# dashboard.net
KiCad netlist of a schematic drawn in EAGLE
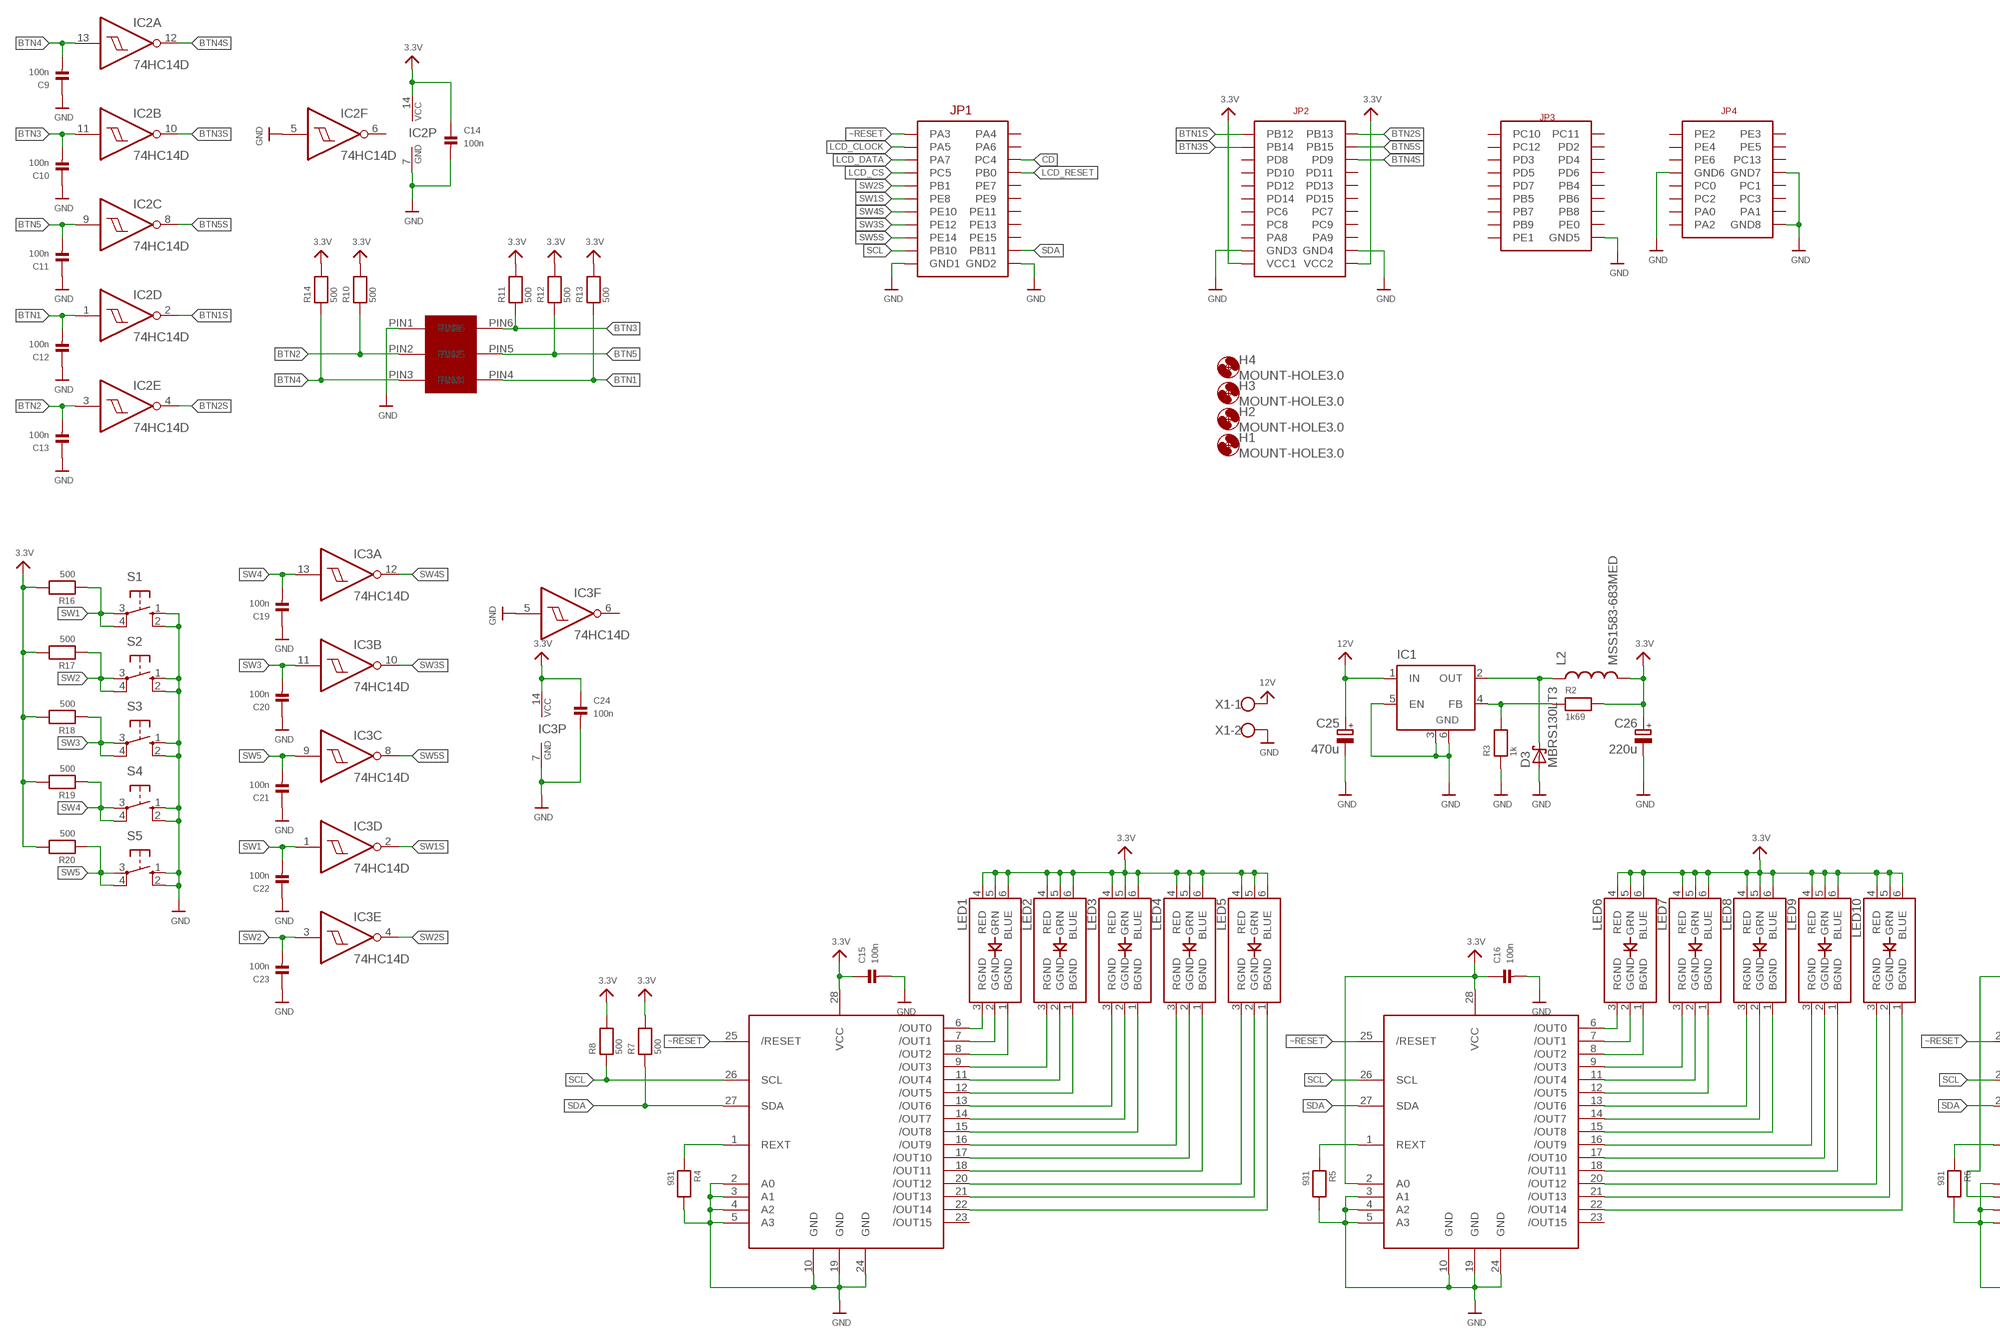
[diagram p0: schematic, sheet 1, part 1 of 2]
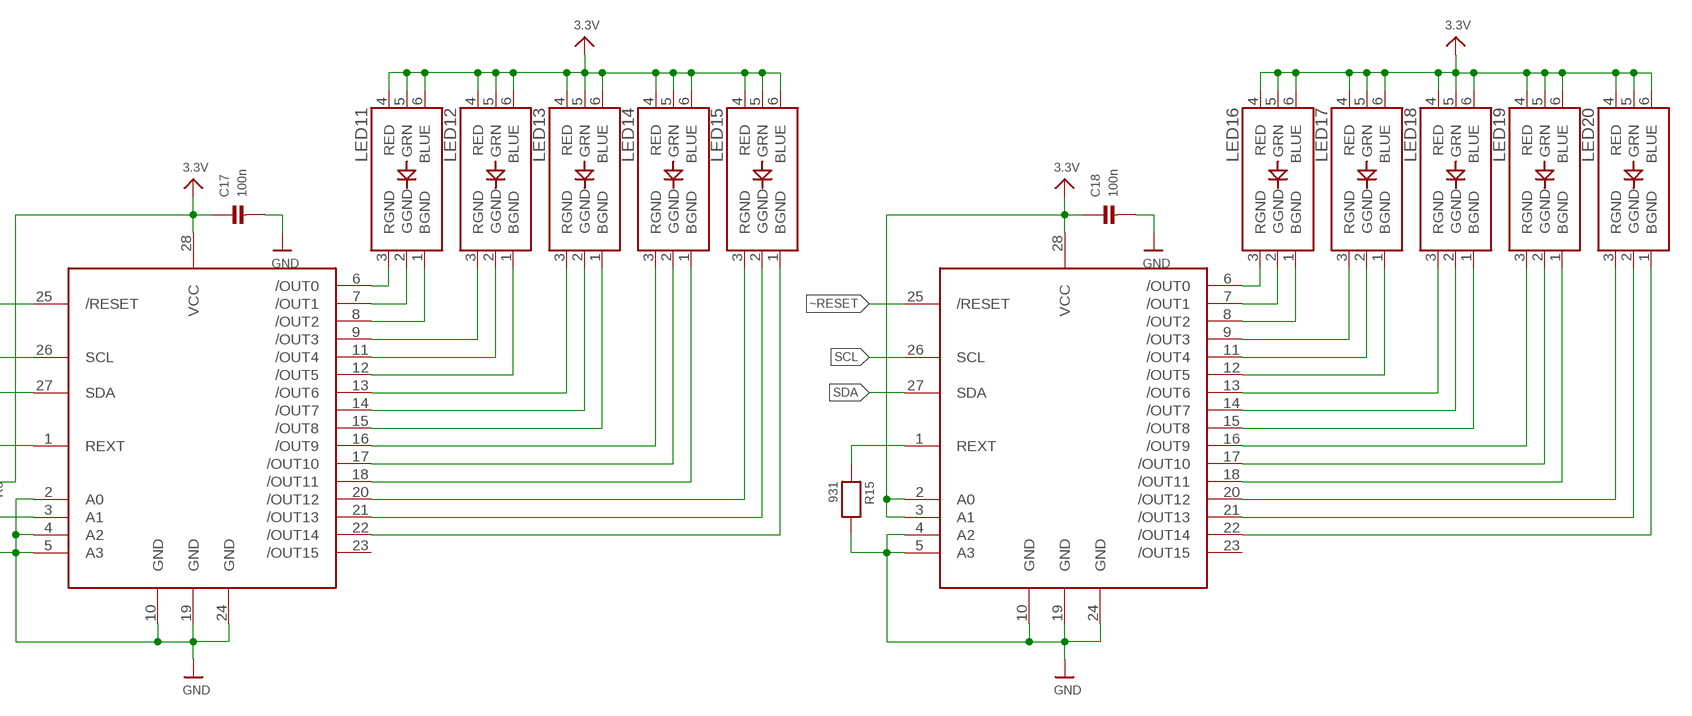
[diagram p1: schematic, sheet 1, part 2 of 2]

(export (version "E")
  (design (tool "Eeschema 10.0.6"))
  (components
    (comp (ref "C9")
      (value "100n")
      (footprint "eagle-import:_0603")
      (libsource (lib "eagle-import") (part "CAP_CERAMIC_0603"))
    )
    (comp (ref "C10")
      (value "100n")
      (footprint "eagle-import:_0603")
      (libsource (lib "eagle-import") (part "CAP_CERAMIC_0603"))
    )
    (comp (ref "C11")
      (value "100n")
      (footprint "eagle-import:_0603")
      (libsource (lib "eagle-import") (part "CAP_CERAMIC_0603"))
    )
    (comp (ref "C12")
      (value "100n")
      (footprint "eagle-import:_0603")
      (libsource (lib "eagle-import") (part "CAP_CERAMIC_0603"))
    )
    (comp (ref "C13")
      (value "100n")
      (footprint "eagle-import:_0603")
      (libsource (lib "eagle-import") (part "CAP_CERAMIC_0603"))
    )
    (comp (ref "C14")
      (value "100n")
      (footprint "eagle-import:_0603")
      (libsource (lib "eagle-import") (part "CAP_CERAMIC_0603"))
    )
    (comp (ref "C15")
      (value "100n")
      (footprint "eagle-import:_0603")
      (libsource (lib "eagle-import") (part "CAP_CERAMIC_0603"))
    )
    (comp (ref "C16")
      (value "100n")
      (footprint "eagle-import:_0603")
      (libsource (lib "eagle-import") (part "CAP_CERAMIC_0603"))
    )
    (comp (ref "C17")
      (value "100n")
      (footprint "eagle-import:_0603")
      (libsource (lib "eagle-import") (part "CAP_CERAMIC_0603"))
    )
    (comp (ref "C18")
      (value "100n")
      (footprint "eagle-import:_0603")
      (libsource (lib "eagle-import") (part "CAP_CERAMIC_0603"))
    )
    (comp (ref "C19")
      (value "100n")
      (footprint "eagle-import:_0603")
      (libsource (lib "eagle-import") (part "CAP_CERAMIC_0603"))
    )
    (comp (ref "C20")
      (value "100n")
      (footprint "eagle-import:_0603")
      (libsource (lib "eagle-import") (part "CAP_CERAMIC_0603"))
    )
    (comp (ref "C21")
      (value "100n")
      (footprint "eagle-import:_0603")
      (libsource (lib "eagle-import") (part "CAP_CERAMIC_0603"))
    )
    (comp (ref "C22")
      (value "100n")
      (footprint "eagle-import:_0603")
      (libsource (lib "eagle-import") (part "CAP_CERAMIC_0603"))
    )
    (comp (ref "C23")
      (value "100n")
      (footprint "eagle-import:_0603")
      (libsource (lib "eagle-import") (part "CAP_CERAMIC_0603"))
    )
    (comp (ref "C24")
      (value "100n")
      (footprint "eagle-import:_0603")
      (libsource (lib "eagle-import") (part "CAP_CERAMIC_0603"))
    )
    (comp (ref "C25")
      (value "470u")
      (footprint "eagle-import:153CLV-1012")
      (libsource (lib "eagle-import") (part "CPOL-EU153CLV-1012"))
    )
    (comp (ref "C26")
      (value "220u")
      (footprint "eagle-import:153CLV-1012")
      (libsource (lib "eagle-import") (part "CPOL-EU153CLV-1012"))
    )
    (comp (ref "D3")
      (value "MBRS130LT3")
      (footprint "eagle-import:SMB")
      (libsource (lib "eagle-import") (part "MBRS130LT3"))
    )
    (comp (ref "H1")
      (value "MOUNT-HOLE3.0")
      (footprint "eagle-import:3,0")
      (libsource (lib "eagle-import") (part "MOUNT-HOLE3.0"))
    )
    (comp (ref "H2")
      (value "MOUNT-HOLE3.0")
      (footprint "eagle-import:3,0")
      (libsource (lib "eagle-import") (part "MOUNT-HOLE3.0"))
    )
    (comp (ref "H3")
      (value "MOUNT-HOLE3.0")
      (footprint "eagle-import:3,0")
      (libsource (lib "eagle-import") (part "MOUNT-HOLE3.0"))
    )
    (comp (ref "H4")
      (value "MOUNT-HOLE3.0")
      (footprint "eagle-import:3,0")
      (libsource (lib "eagle-import") (part "MOUNT-HOLE3.0"))
    )
    (comp (ref "IC1")
      (value "LM2596S")
      (footprint "eagle-import:TO263-5")
      (libsource (lib "eagle-import") (part "LM2596S"))
    )
    (comp (ref "IC2")
      (value "74HC14D")
      (footprint "eagle-import:SO14")
      (libsource (lib "eagle-import") (part "7414DHC"))
    )
    (comp (ref "IC3")
      (value "74HC14D")
      (footprint "eagle-import:SO14")
      (libsource (lib "eagle-import") (part "7414DHC"))
    )
    (comp (ref "L2")
      (value "MSS1583-683MED")
      (footprint "eagle-import:CDRH125")
      (libsource (lib "eagle-import") (part "INDUCTORPWR"))
    )
    (comp (ref "LED1")
      (value "LED_RGB_PLCC6CREE-CLV6A")
      (footprint "eagle-import:RGBLED_PLCC6")
      (libsource (lib "eagle-import") (part "LED_RGB_PLCC6CREE-CLV6A"))
    )
    (comp (ref "LED2")
      (value "LED_RGB_PLCC6CREE-CLV6A")
      (footprint "eagle-import:RGBLED_PLCC6")
      (libsource (lib "eagle-import") (part "LED_RGB_PLCC6CREE-CLV6A"))
    )
    (comp (ref "LED3")
      (value "LED_RGB_PLCC6CREE-CLV6A")
      (footprint "eagle-import:RGBLED_PLCC6")
      (libsource (lib "eagle-import") (part "LED_RGB_PLCC6CREE-CLV6A"))
    )
    (comp (ref "LED4")
      (value "LED_RGB_PLCC6CREE-CLV6A")
      (footprint "eagle-import:RGBLED_PLCC6")
      (libsource (lib "eagle-import") (part "LED_RGB_PLCC6CREE-CLV6A"))
    )
    (comp (ref "LED5")
      (value "LED_RGB_PLCC6CREE-CLV6A")
      (footprint "eagle-import:RGBLED_PLCC6")
      (libsource (lib "eagle-import") (part "LED_RGB_PLCC6CREE-CLV6A"))
    )
    (comp (ref "LED6")
      (value "LED_RGB_PLCC6CREE-CLV6A")
      (footprint "eagle-import:RGBLED_PLCC6")
      (libsource (lib "eagle-import") (part "LED_RGB_PLCC6CREE-CLV6A"))
    )
    (comp (ref "LED7")
      (value "LED_RGB_PLCC6CREE-CLV6A")
      (footprint "eagle-import:RGBLED_PLCC6")
      (libsource (lib "eagle-import") (part "LED_RGB_PLCC6CREE-CLV6A"))
    )
    (comp (ref "LED8")
      (value "LED_RGB_PLCC6CREE-CLV6A")
      (footprint "eagle-import:RGBLED_PLCC6")
      (libsource (lib "eagle-import") (part "LED_RGB_PLCC6CREE-CLV6A"))
    )
    (comp (ref "LED9")
      (value "LED_RGB_PLCC6CREE-CLV6A")
      (footprint "eagle-import:RGBLED_PLCC6")
      (libsource (lib "eagle-import") (part "LED_RGB_PLCC6CREE-CLV6A"))
    )
    (comp (ref "LED10")
      (value "LED_RGB_PLCC6CREE-CLV6A")
      (footprint "eagle-import:RGBLED_PLCC6")
      (libsource (lib "eagle-import") (part "LED_RGB_PLCC6CREE-CLV6A"))
    )
    (comp (ref "LED11")
      (value "LED_RGB_PLCC6CREE-CLV6A")
      (footprint "eagle-import:RGBLED_PLCC6")
      (libsource (lib "eagle-import") (part "LED_RGB_PLCC6CREE-CLV6A"))
    )
    (comp (ref "LED12")
      (value "LED_RGB_PLCC6CREE-CLV6A")
      (footprint "eagle-import:RGBLED_PLCC6")
      (libsource (lib "eagle-import") (part "LED_RGB_PLCC6CREE-CLV6A"))
    )
    (comp (ref "LED13")
      (value "LED_RGB_PLCC6CREE-CLV6A")
      (footprint "eagle-import:RGBLED_PLCC6")
      (libsource (lib "eagle-import") (part "LED_RGB_PLCC6CREE-CLV6A"))
    )
    (comp (ref "LED14")
      (value "LED_RGB_PLCC6CREE-CLV6A")
      (footprint "eagle-import:RGBLED_PLCC6")
      (libsource (lib "eagle-import") (part "LED_RGB_PLCC6CREE-CLV6A"))
    )
    (comp (ref "LED15")
      (value "LED_RGB_PLCC6CREE-CLV6A")
      (footprint "eagle-import:RGBLED_PLCC6")
      (libsource (lib "eagle-import") (part "LED_RGB_PLCC6CREE-CLV6A"))
    )
    (comp (ref "LED16")
      (value "LED_RGB_PLCC6CREE-CLV6A")
      (footprint "eagle-import:RGBLED_PLCC6")
      (libsource (lib "eagle-import") (part "LED_RGB_PLCC6CREE-CLV6A"))
    )
    (comp (ref "LED17")
      (value "LED_RGB_PLCC6CREE-CLV6A")
      (footprint "eagle-import:RGBLED_PLCC6")
      (libsource (lib "eagle-import") (part "LED_RGB_PLCC6CREE-CLV6A"))
    )
    (comp (ref "LED18")
      (value "LED_RGB_PLCC6CREE-CLV6A")
      (footprint "eagle-import:RGBLED_PLCC6")
      (libsource (lib "eagle-import") (part "LED_RGB_PLCC6CREE-CLV6A"))
    )
    (comp (ref "LED19")
      (value "LED_RGB_PLCC6CREE-CLV6A")
      (footprint "eagle-import:RGBLED_PLCC6")
      (libsource (lib "eagle-import") (part "LED_RGB_PLCC6CREE-CLV6A"))
    )
    (comp (ref "LED20")
      (value "LED_RGB_PLCC6CREE-CLV6A")
      (footprint "eagle-import:RGBLED_PLCC6")
      (libsource (lib "eagle-import") (part "LED_RGB_PLCC6CREE-CLV6A"))
    )
    (comp (ref "R2")
      (value "1k69")
      (footprint "eagle-import:_0603")
      (libsource (lib "eagle-import") (part "RESISTOR_0603"))
    )
    (comp (ref "R3")
      (value "1k")
      (footprint "eagle-import:_0603")
      (libsource (lib "eagle-import") (part "RESISTOR_0603"))
    )
    (comp (ref "R4")
      (value "931")
      (footprint "eagle-import:_0603")
      (libsource (lib "eagle-import") (part "RESISTOR_0603"))
    )
    (comp (ref "R5")
      (value "931")
      (footprint "eagle-import:_0603")
      (libsource (lib "eagle-import") (part "RESISTOR_0603"))
    )
    (comp (ref "R6")
      (value "931")
      (footprint "eagle-import:_0603")
      (libsource (lib "eagle-import") (part "RESISTOR_0603"))
    )
    (comp (ref "R7")
      (value "500")
      (footprint "eagle-import:_0603")
      (libsource (lib "eagle-import") (part "RESISTOR_0603"))
    )
    (comp (ref "R8")
      (value "500")
      (footprint "eagle-import:_0603")
      (libsource (lib "eagle-import") (part "RESISTOR_0603"))
    )
    (comp (ref "R10")
      (value "500")
      (footprint "eagle-import:_0603")
      (libsource (lib "eagle-import") (part "RESISTOR_0603"))
    )
    (comp (ref "R11")
      (value "500")
      (footprint "eagle-import:_0603")
      (libsource (lib "eagle-import") (part "RESISTOR_0603"))
    )
    (comp (ref "R12")
      (value "500")
      (footprint "eagle-import:_0603")
      (libsource (lib "eagle-import") (part "RESISTOR_0603"))
    )
    (comp (ref "R13")
      (value "500")
      (footprint "eagle-import:_0603")
      (libsource (lib "eagle-import") (part "RESISTOR_0603"))
    )
    (comp (ref "R14")
      (value "500")
      (footprint "eagle-import:_0603")
      (libsource (lib "eagle-import") (part "RESISTOR_0603"))
    )
    (comp (ref "R15")
      (value "931")
      (footprint "eagle-import:_0603")
      (libsource (lib "eagle-import") (part "RESISTOR_0603"))
    )
    (comp (ref "R16")
      (value "500")
      (footprint "eagle-import:_0603")
      (libsource (lib "eagle-import") (part "RESISTOR_0603"))
    )
    (comp (ref "R17")
      (value "500")
      (footprint "eagle-import:_0603")
      (libsource (lib "eagle-import") (part "RESISTOR_0603"))
    )
    (comp (ref "R18")
      (value "500")
      (footprint "eagle-import:_0603")
      (libsource (lib "eagle-import") (part "RESISTOR_0603"))
    )
    (comp (ref "R19")
      (value "500")
      (footprint "eagle-import:_0603")
      (libsource (lib "eagle-import") (part "RESISTOR_0603"))
    )
    (comp (ref "R20")
      (value "500")
      (footprint "eagle-import:_0603")
      (libsource (lib "eagle-import") (part "RESISTOR_0603"))
    )
    (comp (ref "S1")
      (value "10-XX")
      (footprint "eagle-import:B3F-10XX")
      (fields (field (name "MPN") "B3F-1000"))
      (libsource (lib "eagle-import") (part "10-XX"))
    )
    (comp (ref "S2")
      (value "10-XX")
      (footprint "eagle-import:B3F-10XX")
      (fields (field (name "MPN") "B3F-1000"))
      (libsource (lib "eagle-import") (part "10-XX"))
    )
    (comp (ref "S3")
      (value "10-XX")
      (footprint "eagle-import:B3F-10XX")
      (fields (field (name "MPN") "B3F-1000"))
      (libsource (lib "eagle-import") (part "10-XX"))
    )
    (comp (ref "S4")
      (value "10-XX")
      (footprint "eagle-import:B3F-10XX")
      (fields (field (name "MPN") "B3F-1000"))
      (libsource (lib "eagle-import") (part "10-XX"))
    )
    (comp (ref "S5")
      (value "10-XX")
      (footprint "eagle-import:B3F-10XX")
      (fields
        (field (name "MPN") "B3F-1000")
        (field (name "MPN_1") "B3F-1000")
        (field (name "OC_FARNELL") "176432")
        (field (name "OC_NEWARK") "36M3542")
      )
      (libsource (lib "eagle-import") (part "10-XX"))
    )
    (comp (ref "U$1")
      (value "CPU-BOARD")
      (footprint "eagle-import:CPU-BOARD-JP1")
      (libsource (lib "eagle-import") (part "CPU-BOARD"))
    )
    (comp (ref "U$30")
      (value "TLC59116")
      (footprint "eagle-import:TSSOP28")
      (libsource (lib "eagle-import") (part "TLC59116"))
    )
    (comp (ref "U$33")
      (value "TLC59116")
      (footprint "eagle-import:TSSOP28")
      (libsource (lib "eagle-import") (part "TLC59116"))
    )
    (comp (ref "U$36")
      (value "TLC59116")
      (footprint "eagle-import:TSSOP28")
      (libsource (lib "eagle-import") (part "TLC59116"))
    )
    (comp (ref "U$42")
      (value "MICROFIT6")
      (footprint "eagle-import:MICROFIT6SOCK")
      (libsource (lib "eagle-import") (part "MICROFIT6"))
    )
    (comp (ref "U$51")
      (value "TLC59116")
      (footprint "eagle-import:TSSOP28")
      (libsource (lib "eagle-import") (part "TLC59116"))
    )
    (comp (ref "X1")
      (value "W237-102")
      (footprint "eagle-import:W237-102")
      (fields (field (name "MPN") "237-102"))
      (libsource (lib "eagle-import") (part "W237-102"))
    )
  )
  (nets
    (net (code "1") (name "/~{RESET}") (class "Default")
      (node (ref "U$1") (pin "P$1") (pinfunction "PA3_P$1") (pintype "bidirectional"))
      (node (ref "U$30") (pin "25") (pinfunction "/RESET_25") (pintype "bidirectional"))
      (node (ref "U$33") (pin "25") (pinfunction "/RESET_25") (pintype "bidirectional"))
      (node (ref "U$36") (pin "25") (pinfunction "/RESET_25") (pintype "bidirectional"))
      (node (ref "U$51") (pin "25") (pinfunction "/RESET_25") (pintype "bidirectional"))
    )
    (net (code "2") (name "3.3V") (class "Default")
      (node (ref "C14") (pin "1") (pinfunction "P$1_1") (pintype "passive"))
      (node (ref "C15") (pin "1") (pinfunction "P$1_1") (pintype "passive"))
      (node (ref "C16") (pin "1") (pinfunction "P$1_1") (pintype "passive"))
      (node (ref "C17") (pin "1") (pinfunction "P$1_1") (pintype "passive"))
      (node (ref "C18") (pin "1") (pinfunction "P$1_1") (pintype "passive"))
      (node (ref "C24") (pin "1") (pinfunction "P$1_1") (pintype "passive"))
      (node (ref "C26") (pin "+") (pinfunction "+_+") (pintype "passive"))
      (node (ref "IC2") (pin "14") (pinfunction "VCC_14") (pintype "power_in"))
      (node (ref "IC3") (pin "14") (pinfunction "VCC_14") (pintype "power_in"))
      (node (ref "L2") (pin "2") (pinfunction "2_2") (pintype "passive"))
      (node (ref "LED1") (pin "4") (pinfunction "RED_4") (pintype "bidirectional"))
      (node (ref "LED1") (pin "5") (pinfunction "GRN_5") (pintype "bidirectional"))
      (node (ref "LED1") (pin "6") (pinfunction "BLUE_6") (pintype "bidirectional"))
      (node (ref "LED10") (pin "4") (pinfunction "RED_4") (pintype "bidirectional"))
      (node (ref "LED10") (pin "5") (pinfunction "GRN_5") (pintype "bidirectional"))
      (node (ref "LED10") (pin "6") (pinfunction "BLUE_6") (pintype "bidirectional"))
      (node (ref "LED11") (pin "4") (pinfunction "RED_4") (pintype "bidirectional"))
      (node (ref "LED11") (pin "5") (pinfunction "GRN_5") (pintype "bidirectional"))
      (node (ref "LED11") (pin "6") (pinfunction "BLUE_6") (pintype "bidirectional"))
      (node (ref "LED12") (pin "4") (pinfunction "RED_4") (pintype "bidirectional"))
      (node (ref "LED12") (pin "5") (pinfunction "GRN_5") (pintype "bidirectional"))
      (node (ref "LED12") (pin "6") (pinfunction "BLUE_6") (pintype "bidirectional"))
      (node (ref "LED13") (pin "4") (pinfunction "RED_4") (pintype "bidirectional"))
      (node (ref "LED13") (pin "5") (pinfunction "GRN_5") (pintype "bidirectional"))
      (node (ref "LED13") (pin "6") (pinfunction "BLUE_6") (pintype "bidirectional"))
      (node (ref "LED14") (pin "4") (pinfunction "RED_4") (pintype "bidirectional"))
      (node (ref "LED14") (pin "5") (pinfunction "GRN_5") (pintype "bidirectional"))
      (node (ref "LED14") (pin "6") (pinfunction "BLUE_6") (pintype "bidirectional"))
      (node (ref "LED15") (pin "4") (pinfunction "RED_4") (pintype "bidirectional"))
      (node (ref "LED15") (pin "5") (pinfunction "GRN_5") (pintype "bidirectional"))
      (node (ref "LED15") (pin "6") (pinfunction "BLUE_6") (pintype "bidirectional"))
      (node (ref "LED16") (pin "4") (pinfunction "RED_4") (pintype "bidirectional"))
      (node (ref "LED16") (pin "5") (pinfunction "GRN_5") (pintype "bidirectional"))
      (node (ref "LED16") (pin "6") (pinfunction "BLUE_6") (pintype "bidirectional"))
      (node (ref "LED17") (pin "4") (pinfunction "RED_4") (pintype "bidirectional"))
      (node (ref "LED17") (pin "5") (pinfunction "GRN_5") (pintype "bidirectional"))
      (node (ref "LED17") (pin "6") (pinfunction "BLUE_6") (pintype "bidirectional"))
      (node (ref "LED18") (pin "4") (pinfunction "RED_4") (pintype "bidirectional"))
      (node (ref "LED18") (pin "5") (pinfunction "GRN_5") (pintype "bidirectional"))
      (node (ref "LED18") (pin "6") (pinfunction "BLUE_6") (pintype "bidirectional"))
      (node (ref "LED19") (pin "4") (pinfunction "RED_4") (pintype "bidirectional"))
      (node (ref "LED19") (pin "5") (pinfunction "GRN_5") (pintype "bidirectional"))
      (node (ref "LED19") (pin "6") (pinfunction "BLUE_6") (pintype "bidirectional"))
      (node (ref "LED2") (pin "4") (pinfunction "RED_4") (pintype "bidirectional"))
      (node (ref "LED2") (pin "5") (pinfunction "GRN_5") (pintype "bidirectional"))
      (node (ref "LED2") (pin "6") (pinfunction "BLUE_6") (pintype "bidirectional"))
      (node (ref "LED20") (pin "4") (pinfunction "RED_4") (pintype "bidirectional"))
      (node (ref "LED20") (pin "5") (pinfunction "GRN_5") (pintype "bidirectional"))
      (node (ref "LED20") (pin "6") (pinfunction "BLUE_6") (pintype "bidirectional"))
      (node (ref "LED3") (pin "4") (pinfunction "RED_4") (pintype "bidirectional"))
      (node (ref "LED3") (pin "5") (pinfunction "GRN_5") (pintype "bidirectional"))
      (node (ref "LED3") (pin "6") (pinfunction "BLUE_6") (pintype "bidirectional"))
      (node (ref "LED4") (pin "4") (pinfunction "RED_4") (pintype "bidirectional"))
      (node (ref "LED4") (pin "5") (pinfunction "GRN_5") (pintype "bidirectional"))
      (node (ref "LED4") (pin "6") (pinfunction "BLUE_6") (pintype "bidirectional"))
      (node (ref "LED5") (pin "4") (pinfunction "RED_4") (pintype "bidirectional"))
      (node (ref "LED5") (pin "5") (pinfunction "GRN_5") (pintype "bidirectional"))
      (node (ref "LED5") (pin "6") (pinfunction "BLUE_6") (pintype "bidirectional"))
      (node (ref "LED6") (pin "4") (pinfunction "RED_4") (pintype "bidirectional"))
      (node (ref "LED6") (pin "5") (pinfunction "GRN_5") (pintype "bidirectional"))
      (node (ref "LED6") (pin "6") (pinfunction "BLUE_6") (pintype "bidirectional"))
      (node (ref "LED7") (pin "4") (pinfunction "RED_4") (pintype "bidirectional"))
      (node (ref "LED7") (pin "5") (pinfunction "GRN_5") (pintype "bidirectional"))
      (node (ref "LED7") (pin "6") (pinfunction "BLUE_6") (pintype "bidirectional"))
      (node (ref "LED8") (pin "4") (pinfunction "RED_4") (pintype "bidirectional"))
      (node (ref "LED8") (pin "5") (pinfunction "GRN_5") (pintype "bidirectional"))
      (node (ref "LED8") (pin "6") (pinfunction "BLUE_6") (pintype "bidirectional"))
      (node (ref "LED9") (pin "4") (pinfunction "RED_4") (pintype "bidirectional"))
      (node (ref "LED9") (pin "5") (pinfunction "GRN_5") (pintype "bidirectional"))
      (node (ref "LED9") (pin "6") (pinfunction "BLUE_6") (pintype "bidirectional"))
      (node (ref "R10") (pin "2") (pinfunction "2_2") (pintype "passive"))
      (node (ref "R11") (pin "2") (pinfunction "2_2") (pintype "passive"))
      (node (ref "R12") (pin "2") (pinfunction "2_2") (pintype "passive"))
      (node (ref "R13") (pin "2") (pinfunction "2_2") (pintype "passive"))
      (node (ref "R14") (pin "2") (pinfunction "2_2") (pintype "passive"))
      (node (ref "R16") (pin "2") (pinfunction "2_2") (pintype "passive"))
      (node (ref "R17") (pin "2") (pinfunction "2_2") (pintype "passive"))
      (node (ref "R18") (pin "2") (pinfunction "2_2") (pintype "passive"))
      (node (ref "R19") (pin "2") (pinfunction "2_2") (pintype "passive"))
      (node (ref "R2") (pin "2") (pinfunction "2_2") (pintype "passive"))
      (node (ref "R20") (pin "2") (pinfunction "2_2") (pintype "passive"))
      (node (ref "R7") (pin "2") (pinfunction "2_2") (pintype "passive"))
      (node (ref "R8") (pin "2") (pinfunction "2_2") (pintype "passive"))
      (node (ref "U$1") (pin "P$43") (pinfunction "VCC1_P$43") (pintype "bidirectional"))
      (node (ref "U$1") (pin "P$44") (pinfunction "VCC2_P$44") (pintype "bidirectional"))
      (node (ref "U$30") (pin "28") (pinfunction "VCC_28") (pintype "bidirectional"))
      (node (ref "U$33") (pin "2") (pinfunction "A0_2") (pintype "bidirectional"))
      (node (ref "U$33") (pin "28") (pinfunction "VCC_28") (pintype "bidirectional"))
      (node (ref "U$36") (pin "28") (pinfunction "VCC_28") (pintype "bidirectional"))
      (node (ref "U$36") (pin "3") (pinfunction "A1_3") (pintype "bidirectional"))
      (node (ref "U$51") (pin "2") (pinfunction "A0_2") (pintype "bidirectional"))
      (node (ref "U$51") (pin "28") (pinfunction "VCC_28") (pintype "bidirectional"))
      (node (ref "U$51") (pin "3") (pinfunction "A1_3") (pintype "bidirectional"))
    )
    (net (code "3") (name "12V") (class "Default")
      (node (ref "C25") (pin "+") (pinfunction "+_+") (pintype "passive"))
      (node (ref "IC1") (pin "1") (pinfunction "IN_1") (pintype "input"))
      (node (ref "X1") (pin "1") (pinfunction "KL_1") (pintype "passive"))
    )
    (net (code "4") (name "BTN1") (class "Default")
      (node (ref "C12") (pin "2") (pinfunction "P$2_2") (pintype "passive"))
      (node (ref "IC2") (pin "1") (pinfunction "I_1") (pintype "input"))
      (node (ref "R13") (pin "1") (pinfunction "1_1") (pintype "passive"))
      (node (ref "U$42") (pin "PIN4") (pinfunction "PIN4_PIN4") (pintype "bidirectional"))
    )
    (net (code "5") (name "BTN1S") (class "Default")
      (node (ref "IC2") (pin "2") (pinfunction "O_2") (pintype "output"))
      (node (ref "U$1") (pin "P$23") (pinfunction "PB12_P$23") (pintype "bidirectional"))
    )
    (net (code "6") (name "BTN2") (class "Default")
      (node (ref "C13") (pin "2") (pinfunction "P$2_2") (pintype "passive"))
      (node (ref "IC2") (pin "3") (pinfunction "I_3") (pintype "input"))
      (node (ref "R10") (pin "1") (pinfunction "1_1") (pintype "passive"))
      (node (ref "U$42") (pin "PIN2") (pinfunction "PIN2_PIN2") (pintype "bidirectional"))
    )
    (net (code "7") (name "BTN2S") (class "Default")
      (node (ref "IC2") (pin "4") (pinfunction "O_4") (pintype "output"))
      (node (ref "U$1") (pin "P$24") (pinfunction "PB13_P$24") (pintype "bidirectional"))
    )
    (net (code "8") (name "BTN3") (class "Default")
      (node (ref "C10") (pin "2") (pinfunction "P$2_2") (pintype "passive"))
      (node (ref "IC2") (pin "11") (pinfunction "I_11") (pintype "input"))
      (node (ref "R11") (pin "1") (pinfunction "1_1") (pintype "passive"))
      (node (ref "U$42") (pin "PIN6") (pinfunction "PIN6_PIN6") (pintype "bidirectional"))
    )
    (net (code "9") (name "BTN3S") (class "Default")
      (node (ref "IC2") (pin "10") (pinfunction "O_10") (pintype "output"))
      (node (ref "U$1") (pin "P$25") (pinfunction "PB14_P$25") (pintype "bidirectional"))
    )
    (net (code "10") (name "BTN4") (class "Default")
      (node (ref "C9") (pin "2") (pinfunction "P$2_2") (pintype "passive"))
      (node (ref "IC2") (pin "13") (pinfunction "I_13") (pintype "input"))
      (node (ref "R14") (pin "1") (pinfunction "1_1") (pintype "passive"))
      (node (ref "U$42") (pin "PIN3") (pinfunction "PIN3_PIN3") (pintype "bidirectional"))
    )
    (net (code "11") (name "BTN4S") (class "Default")
      (node (ref "IC2") (pin "12") (pinfunction "O_12") (pintype "output"))
      (node (ref "U$1") (pin "P$28") (pinfunction "PD9_P$28") (pintype "bidirectional"))
    )
    (net (code "12") (name "BTN5") (class "Default")
      (node (ref "C11") (pin "2") (pinfunction "P$2_2") (pintype "passive"))
      (node (ref "IC2") (pin "9") (pinfunction "I_9") (pintype "input"))
      (node (ref "R12") (pin "1") (pinfunction "1_1") (pintype "passive"))
      (node (ref "U$42") (pin "PIN5") (pinfunction "PIN5_PIN5") (pintype "bidirectional"))
    )
    (net (code "13") (name "BTN5S") (class "Default")
      (node (ref "IC2") (pin "8") (pinfunction "O_8") (pintype "output"))
      (node (ref "U$1") (pin "P$26") (pinfunction "PB15_P$26") (pintype "bidirectional"))
    )
    (net (code "14") (name "CD") (class "Default")
      (node (ref "U$1") (pin "P$6") (pinfunction "PC4_P$6") (pintype "bidirectional"))
    )
    (net (code "15") (name "GND") (class "Default")
      (node (ref "C10") (pin "1") (pinfunction "P$1_1") (pintype "passive"))
      (node (ref "C11") (pin "1") (pinfunction "P$1_1") (pintype "passive"))
      (node (ref "C12") (pin "1") (pinfunction "P$1_1") (pintype "passive"))
      (node (ref "C13") (pin "1") (pinfunction "P$1_1") (pintype "passive"))
      (node (ref "C14") (pin "2") (pinfunction "P$2_2") (pintype "passive"))
      (node (ref "C15") (pin "2") (pinfunction "P$2_2") (pintype "passive"))
      (node (ref "C16") (pin "2") (pinfunction "P$2_2") (pintype "passive"))
      (node (ref "C17") (pin "2") (pinfunction "P$2_2") (pintype "passive"))
      (node (ref "C18") (pin "2") (pinfunction "P$2_2") (pintype "passive"))
      (node (ref "C19") (pin "1") (pinfunction "P$1_1") (pintype "passive"))
      (node (ref "C20") (pin "1") (pinfunction "P$1_1") (pintype "passive"))
      (node (ref "C21") (pin "1") (pinfunction "P$1_1") (pintype "passive"))
      (node (ref "C22") (pin "1") (pinfunction "P$1_1") (pintype "passive"))
      (node (ref "C23") (pin "1") (pinfunction "P$1_1") (pintype "passive"))
      (node (ref "C24") (pin "2") (pinfunction "P$2_2") (pintype "passive"))
      (node (ref "C25") (pin "-") (pinfunction "-_-") (pintype "passive"))
      (node (ref "C26") (pin "-") (pinfunction "-_-") (pintype "passive"))
      (node (ref "C9") (pin "1") (pinfunction "P$1_1") (pintype "passive"))
      (node (ref "D3") (pin "A") (pinfunction "A_A") (pintype "passive"))
      (node (ref "IC1") (pin "3") (pinfunction "GND_3") (pintype "power_in"))
      (node (ref "IC1") (pin "5") (pinfunction "EN_5") (pintype "input"))
      (node (ref "IC1") (pin "6") (pinfunction "GND_6") (pintype "power_in"))
      (node (ref "IC2") (pin "5") (pinfunction "I_5") (pintype "input"))
      (node (ref "IC2") (pin "7") (pinfunction "GND_7") (pintype "power_in"))
      (node (ref "IC3") (pin "5") (pinfunction "I_5") (pintype "input"))
      (node (ref "IC3") (pin "7") (pinfunction "GND_7") (pintype "power_in"))
      (node (ref "R15") (pin "2") (pinfunction "2_2") (pintype "passive"))
      (node (ref "R3") (pin "1") (pinfunction "1_1") (pintype "passive"))
      (node (ref "R4") (pin "2") (pinfunction "2_2") (pintype "passive"))
      (node (ref "R5") (pin "2") (pinfunction "2_2") (pintype "passive"))
      (node (ref "R6") (pin "2") (pinfunction "2_2") (pintype "passive"))
      (node (ref "S1") (pin "1") (pinfunction "S_1") (pintype "passive"))
      (node (ref "S1") (pin "2") (pinfunction "S1_2") (pintype "passive"))
      (node (ref "S2") (pin "1") (pinfunction "S_1") (pintype "passive"))
      (node (ref "S2") (pin "2") (pinfunction "S1_2") (pintype "passive"))
      (node (ref "S3") (pin "1") (pinfunction "S_1") (pintype "passive"))
      (node (ref "S3") (pin "2") (pinfunction "S1_2") (pintype "passive"))
      (node (ref "S4") (pin "1") (pinfunction "S_1") (pintype "passive"))
      (node (ref "S4") (pin "2") (pinfunction "S1_2") (pintype "passive"))
      (node (ref "S5") (pin "1") (pinfunction "S_1") (pintype "passive"))
      (node (ref "S5") (pin "2") (pinfunction "S1_2") (pintype "passive"))
      (node (ref "U$1") (pin "P$19") (pinfunction "GND1_P$19") (pintype "bidirectional"))
      (node (ref "U$1") (pin "P$20") (pinfunction "GND2_P$20") (pintype "bidirectional"))
      (node (ref "U$1") (pin "P$41") (pinfunction "GND3_P$41") (pintype "bidirectional"))
      (node (ref "U$1") (pin "P$42") (pinfunction "GND4_P$42") (pintype "bidirectional"))
      (node (ref "U$1") (pin "P$62") (pinfunction "GND5_P$62") (pintype "bidirectional"))
      (node (ref "U$1") (pin "P$69") (pinfunction "GND6_P$69") (pintype "bidirectional"))
      (node (ref "U$1") (pin "P$70") (pinfunction "GND7_P$70") (pintype "bidirectional"))
      (node (ref "U$1") (pin "P$78") (pinfunction "GND8_P$78") (pintype "bidirectional"))
      (node (ref "U$30") (pin "10") (pinfunction "GND_10") (pintype "bidirectional"))
      (node (ref "U$30") (pin "19") (pinfunction "GND_19") (pintype "bidirectional"))
      (node (ref "U$30") (pin "2") (pinfunction "A0_2") (pintype "bidirectional"))
      (node (ref "U$30") (pin "24") (pinfunction "GND_24") (pintype "bidirectional"))
      (node (ref "U$30") (pin "3") (pinfunction "A1_3") (pintype "bidirectional"))
      (node (ref "U$30") (pin "4") (pinfunction "A2_4") (pintype "bidirectional"))
      (node (ref "U$30") (pin "5") (pinfunction "A3_5") (pintype "bidirectional"))
      (node (ref "U$33") (pin "10") (pinfunction "GND_10") (pintype "bidirectional"))
      (node (ref "U$33") (pin "19") (pinfunction "GND_19") (pintype "bidirectional"))
      (node (ref "U$33") (pin "24") (pinfunction "GND_24") (pintype "bidirectional"))
      (node (ref "U$33") (pin "3") (pinfunction "A1_3") (pintype "bidirectional"))
      (node (ref "U$33") (pin "4") (pinfunction "A2_4") (pintype "bidirectional"))
      (node (ref "U$33") (pin "5") (pinfunction "A3_5") (pintype "bidirectional"))
      (node (ref "U$36") (pin "10") (pinfunction "GND_10") (pintype "bidirectional"))
      (node (ref "U$36") (pin "19") (pinfunction "GND_19") (pintype "bidirectional"))
      (node (ref "U$36") (pin "2") (pinfunction "A0_2") (pintype "bidirectional"))
      (node (ref "U$36") (pin "24") (pinfunction "GND_24") (pintype "bidirectional"))
      (node (ref "U$36") (pin "4") (pinfunction "A2_4") (pintype "bidirectional"))
      (node (ref "U$36") (pin "5") (pinfunction "A3_5") (pintype "bidirectional"))
      (node (ref "U$42") (pin "PIN1") (pinfunction "PIN1_PIN1") (pintype "bidirectional"))
      (node (ref "U$51") (pin "10") (pinfunction "GND_10") (pintype "bidirectional"))
      (node (ref "U$51") (pin "19") (pinfunction "GND_19") (pintype "bidirectional"))
      (node (ref "U$51") (pin "24") (pinfunction "GND_24") (pintype "bidirectional"))
      (node (ref "U$51") (pin "4") (pinfunction "A2_4") (pintype "bidirectional"))
      (node (ref "U$51") (pin "5") (pinfunction "A3_5") (pintype "bidirectional"))
      (node (ref "X1") (pin "2") (pinfunction "KL_2") (pintype "passive"))
    )
    (net (code "16") (name "LCD_CLOCK") (class "Default")
      (node (ref "U$1") (pin "P$3") (pinfunction "PA5_P$3") (pintype "bidirectional"))
    )
    (net (code "17") (name "LCD_CS") (class "Default")
      (node (ref "U$1") (pin "P$7") (pinfunction "PC5_P$7") (pintype "bidirectional"))
    )
    (net (code "18") (name "LCD_DATA") (class "Default")
      (node (ref "U$1") (pin "P$5") (pinfunction "PA7_P$5") (pintype "bidirectional"))
    )
    (net (code "19") (name "LCD_RESET") (class "Default")
      (node (ref "U$1") (pin "P$8") (pinfunction "PB0_P$8") (pintype "bidirectional"))
    )
    (net (code "20") (name "Net-(IC1-FB)") (class "Default")
      (node (ref "IC1") (pin "4") (pinfunction "FB_4") (pintype "input"))
      (node (ref "R2") (pin "1") (pinfunction "1_1") (pintype "passive"))
      (node (ref "R3") (pin "2") (pinfunction "2_2") (pintype "passive"))
    )
    (net (code "21") (name "Net-(IC1-OUT)") (class "Default")
      (node (ref "D3") (pin "C") (pinfunction "C_C") (pintype "passive"))
      (node (ref "IC1") (pin "2") (pinfunction "OUT_2") (pintype "output"))
      (node (ref "L2") (pin "1") (pinfunction "1_1") (pintype "passive"))
    )
    (net (code "22") (name "Net-(LED1-BGND)") (class "Default")
      (node (ref "LED1") (pin "1") (pinfunction "BGND_1") (pintype "power_in"))
      (node (ref "U$30") (pin "8") (pinfunction "/OUT2_8") (pintype "bidirectional"))
    )
    (net (code "23") (name "Net-(LED1-GGND)") (class "Default")
      (node (ref "LED1") (pin "2") (pinfunction "GGND_2") (pintype "power_in"))
      (node (ref "U$30") (pin "7") (pinfunction "/OUT1_7") (pintype "bidirectional"))
    )
    (net (code "24") (name "Net-(LED1-RGND)") (class "Default")
      (node (ref "LED1") (pin "3") (pinfunction "RGND_3") (pintype "power_in"))
      (node (ref "U$30") (pin "6") (pinfunction "/OUT0_6") (pintype "bidirectional"))
    )
    (net (code "25") (name "Net-(LED2-BGND)") (class "Default")
      (node (ref "LED2") (pin "1") (pinfunction "BGND_1") (pintype "power_in"))
      (node (ref "U$30") (pin "12") (pinfunction "/OUT5_12") (pintype "bidirectional"))
    )
    (net (code "26") (name "Net-(LED2-GGND)") (class "Default")
      (node (ref "LED2") (pin "2") (pinfunction "GGND_2") (pintype "power_in"))
      (node (ref "U$30") (pin "11") (pinfunction "/OUT4_11") (pintype "bidirectional"))
    )
    (net (code "27") (name "Net-(LED2-RGND)") (class "Default")
      (node (ref "LED2") (pin "3") (pinfunction "RGND_3") (pintype "power_in"))
      (node (ref "U$30") (pin "9") (pinfunction "/OUT3_9") (pintype "bidirectional"))
    )
    (net (code "28") (name "Net-(LED3-BGND)") (class "Default")
      (node (ref "LED3") (pin "1") (pinfunction "BGND_1") (pintype "power_in"))
      (node (ref "U$30") (pin "15") (pinfunction "/OUT8_15") (pintype "bidirectional"))
    )
    (net (code "29") (name "Net-(LED3-GGND)") (class "Default")
      (node (ref "LED3") (pin "2") (pinfunction "GGND_2") (pintype "power_in"))
      (node (ref "U$30") (pin "14") (pinfunction "/OUT7_14") (pintype "bidirectional"))
    )
    (net (code "30") (name "Net-(LED3-RGND)") (class "Default")
      (node (ref "LED3") (pin "3") (pinfunction "RGND_3") (pintype "power_in"))
      (node (ref "U$30") (pin "13") (pinfunction "/OUT6_13") (pintype "bidirectional"))
    )
    (net (code "31") (name "Net-(LED4-BGND)") (class "Default")
      (node (ref "LED4") (pin "1") (pinfunction "BGND_1") (pintype "power_in"))
      (node (ref "U$30") (pin "18") (pinfunction "/OUT11_18") (pintype "bidirectional"))
    )
    (net (code "32") (name "Net-(LED4-GGND)") (class "Default")
      (node (ref "LED4") (pin "2") (pinfunction "GGND_2") (pintype "power_in"))
      (node (ref "U$30") (pin "17") (pinfunction "/OUT10_17") (pintype "bidirectional"))
    )
    (net (code "33") (name "Net-(LED4-RGND)") (class "Default")
      (node (ref "LED4") (pin "3") (pinfunction "RGND_3") (pintype "power_in"))
      (node (ref "U$30") (pin "16") (pinfunction "/OUT9_16") (pintype "bidirectional"))
    )
    (net (code "34") (name "Net-(LED5-BGND)") (class "Default")
      (node (ref "LED5") (pin "1") (pinfunction "BGND_1") (pintype "power_in"))
      (node (ref "U$30") (pin "22") (pinfunction "/OUT14_22") (pintype "bidirectional"))
    )
    (net (code "35") (name "Net-(LED5-GGND)") (class "Default")
      (node (ref "LED5") (pin "2") (pinfunction "GGND_2") (pintype "power_in"))
      (node (ref "U$30") (pin "21") (pinfunction "/OUT13_21") (pintype "bidirectional"))
    )
    (net (code "36") (name "Net-(LED5-RGND)") (class "Default")
      (node (ref "LED5") (pin "3") (pinfunction "RGND_3") (pintype "power_in"))
      (node (ref "U$30") (pin "20") (pinfunction "/OUT12_20") (pintype "bidirectional"))
    )
    (net (code "37") (name "Net-(LED6-BGND)") (class "Default")
      (node (ref "LED6") (pin "1") (pinfunction "BGND_1") (pintype "power_in"))
      (node (ref "U$33") (pin "8") (pinfunction "/OUT2_8") (pintype "bidirectional"))
    )
    (net (code "38") (name "Net-(LED6-GGND)") (class "Default")
      (node (ref "LED6") (pin "2") (pinfunction "GGND_2") (pintype "power_in"))
      (node (ref "U$33") (pin "7") (pinfunction "/OUT1_7") (pintype "bidirectional"))
    )
    (net (code "39") (name "Net-(LED6-RGND)") (class "Default")
      (node (ref "LED6") (pin "3") (pinfunction "RGND_3") (pintype "power_in"))
      (node (ref "U$33") (pin "6") (pinfunction "/OUT0_6") (pintype "bidirectional"))
    )
    (net (code "40") (name "Net-(LED7-BGND)") (class "Default")
      (node (ref "LED7") (pin "1") (pinfunction "BGND_1") (pintype "power_in"))
      (node (ref "U$33") (pin "12") (pinfunction "/OUT5_12") (pintype "bidirectional"))
    )
    (net (code "41") (name "Net-(LED7-GGND)") (class "Default")
      (node (ref "LED7") (pin "2") (pinfunction "GGND_2") (pintype "power_in"))
      (node (ref "U$33") (pin "11") (pinfunction "/OUT4_11") (pintype "bidirectional"))
    )
    (net (code "42") (name "Net-(LED7-RGND)") (class "Default")
      (node (ref "LED7") (pin "3") (pinfunction "RGND_3") (pintype "power_in"))
      (node (ref "U$33") (pin "9") (pinfunction "/OUT3_9") (pintype "bidirectional"))
    )
    (net (code "43") (name "Net-(LED8-BGND)") (class "Default")
      (node (ref "LED8") (pin "1") (pinfunction "BGND_1") (pintype "power_in"))
      (node (ref "U$33") (pin "15") (pinfunction "/OUT8_15") (pintype "bidirectional"))
    )
    (net (code "44") (name "Net-(LED8-GGND)") (class "Default")
      (node (ref "LED8") (pin "2") (pinfunction "GGND_2") (pintype "power_in"))
      (node (ref "U$33") (pin "14") (pinfunction "/OUT7_14") (pintype "bidirectional"))
    )
    (net (code "45") (name "Net-(LED8-RGND)") (class "Default")
      (node (ref "LED8") (pin "3") (pinfunction "RGND_3") (pintype "power_in"))
      (node (ref "U$33") (pin "13") (pinfunction "/OUT6_13") (pintype "bidirectional"))
    )
    (net (code "46") (name "Net-(LED9-BGND)") (class "Default")
      (node (ref "LED9") (pin "1") (pinfunction "BGND_1") (pintype "power_in"))
      (node (ref "U$33") (pin "18") (pinfunction "/OUT11_18") (pintype "bidirectional"))
    )
    (net (code "47") (name "Net-(LED9-GGND)") (class "Default")
      (node (ref "LED9") (pin "2") (pinfunction "GGND_2") (pintype "power_in"))
      (node (ref "U$33") (pin "17") (pinfunction "/OUT10_17") (pintype "bidirectional"))
    )
    (net (code "48") (name "Net-(LED9-RGND)") (class "Default")
      (node (ref "LED9") (pin "3") (pinfunction "RGND_3") (pintype "power_in"))
      (node (ref "U$33") (pin "16") (pinfunction "/OUT9_16") (pintype "bidirectional"))
    )
    (net (code "49") (name "Net-(LED10-BGND)") (class "Default")
      (node (ref "LED10") (pin "1") (pinfunction "BGND_1") (pintype "power_in"))
      (node (ref "U$33") (pin "22") (pinfunction "/OUT14_22") (pintype "bidirectional"))
    )
    (net (code "50") (name "Net-(LED10-GGND)") (class "Default")
      (node (ref "LED10") (pin "2") (pinfunction "GGND_2") (pintype "power_in"))
      (node (ref "U$33") (pin "21") (pinfunction "/OUT13_21") (pintype "bidirectional"))
    )
    (net (code "51") (name "Net-(LED10-RGND)") (class "Default")
      (node (ref "LED10") (pin "3") (pinfunction "RGND_3") (pintype "power_in"))
      (node (ref "U$33") (pin "20") (pinfunction "/OUT12_20") (pintype "bidirectional"))
    )
    (net (code "52") (name "Net-(LED11-BGND)") (class "Default")
      (node (ref "LED11") (pin "1") (pinfunction "BGND_1") (pintype "power_in"))
      (node (ref "U$36") (pin "8") (pinfunction "/OUT2_8") (pintype "bidirectional"))
    )
    (net (code "53") (name "Net-(LED11-GGND)") (class "Default")
      (node (ref "LED11") (pin "2") (pinfunction "GGND_2") (pintype "power_in"))
      (node (ref "U$36") (pin "7") (pinfunction "/OUT1_7") (pintype "bidirectional"))
    )
    (net (code "54") (name "Net-(LED11-RGND)") (class "Default")
      (node (ref "LED11") (pin "3") (pinfunction "RGND_3") (pintype "power_in"))
      (node (ref "U$36") (pin "6") (pinfunction "/OUT0_6") (pintype "bidirectional"))
    )
    (net (code "55") (name "Net-(LED12-BGND)") (class "Default")
      (node (ref "LED12") (pin "1") (pinfunction "BGND_1") (pintype "power_in"))
      (node (ref "U$36") (pin "12") (pinfunction "/OUT5_12") (pintype "bidirectional"))
    )
    (net (code "56") (name "Net-(LED12-GGND)") (class "Default")
      (node (ref "LED12") (pin "2") (pinfunction "GGND_2") (pintype "power_in"))
      (node (ref "U$36") (pin "11") (pinfunction "/OUT4_11") (pintype "bidirectional"))
    )
    (net (code "57") (name "Net-(LED12-RGND)") (class "Default")
      (node (ref "LED12") (pin "3") (pinfunction "RGND_3") (pintype "power_in"))
      (node (ref "U$36") (pin "9") (pinfunction "/OUT3_9") (pintype "bidirectional"))
    )
    (net (code "58") (name "Net-(LED13-BGND)") (class "Default")
      (node (ref "LED13") (pin "1") (pinfunction "BGND_1") (pintype "power_in"))
      (node (ref "U$36") (pin "15") (pinfunction "/OUT8_15") (pintype "bidirectional"))
    )
    (net (code "59") (name "Net-(LED13-GGND)") (class "Default")
      (node (ref "LED13") (pin "2") (pinfunction "GGND_2") (pintype "power_in"))
      (node (ref "U$36") (pin "14") (pinfunction "/OUT7_14") (pintype "bidirectional"))
    )
    (net (code "60") (name "Net-(LED13-RGND)") (class "Default")
      (node (ref "LED13") (pin "3") (pinfunction "RGND_3") (pintype "power_in"))
      (node (ref "U$36") (pin "13") (pinfunction "/OUT6_13") (pintype "bidirectional"))
    )
    (net (code "61") (name "Net-(LED14-BGND)") (class "Default")
      (node (ref "LED14") (pin "1") (pinfunction "BGND_1") (pintype "power_in"))
      (node (ref "U$36") (pin "18") (pinfunction "/OUT11_18") (pintype "bidirectional"))
    )
    (net (code "62") (name "Net-(LED14-GGND)") (class "Default")
      (node (ref "LED14") (pin "2") (pinfunction "GGND_2") (pintype "power_in"))
      (node (ref "U$36") (pin "17") (pinfunction "/OUT10_17") (pintype "bidirectional"))
    )
    (net (code "63") (name "Net-(LED14-RGND)") (class "Default")
      (node (ref "LED14") (pin "3") (pinfunction "RGND_3") (pintype "power_in"))
      (node (ref "U$36") (pin "16") (pinfunction "/OUT9_16") (pintype "bidirectional"))
    )
    (net (code "64") (name "Net-(LED15-BGND)") (class "Default")
      (node (ref "LED15") (pin "1") (pinfunction "BGND_1") (pintype "power_in"))
      (node (ref "U$36") (pin "22") (pinfunction "/OUT14_22") (pintype "bidirectional"))
    )
    (net (code "65") (name "Net-(LED15-GGND)") (class "Default")
      (node (ref "LED15") (pin "2") (pinfunction "GGND_2") (pintype "power_in"))
      (node (ref "U$36") (pin "21") (pinfunction "/OUT13_21") (pintype "bidirectional"))
    )
    (net (code "66") (name "Net-(LED15-RGND)") (class "Default")
      (node (ref "LED15") (pin "3") (pinfunction "RGND_3") (pintype "power_in"))
      (node (ref "U$36") (pin "20") (pinfunction "/OUT12_20") (pintype "bidirectional"))
    )
    (net (code "67") (name "Net-(LED16-BGND)") (class "Default")
      (node (ref "LED16") (pin "1") (pinfunction "BGND_1") (pintype "power_in"))
      (node (ref "U$51") (pin "8") (pinfunction "/OUT2_8") (pintype "bidirectional"))
    )
    (net (code "68") (name "Net-(LED16-GGND)") (class "Default")
      (node (ref "LED16") (pin "2") (pinfunction "GGND_2") (pintype "power_in"))
      (node (ref "U$51") (pin "7") (pinfunction "/OUT1_7") (pintype "bidirectional"))
    )
    (net (code "69") (name "Net-(LED16-RGND)") (class "Default")
      (node (ref "LED16") (pin "3") (pinfunction "RGND_3") (pintype "power_in"))
      (node (ref "U$51") (pin "6") (pinfunction "/OUT0_6") (pintype "bidirectional"))
    )
    (net (code "70") (name "Net-(LED17-BGND)") (class "Default")
      (node (ref "LED17") (pin "1") (pinfunction "BGND_1") (pintype "power_in"))
      (node (ref "U$51") (pin "12") (pinfunction "/OUT5_12") (pintype "bidirectional"))
    )
    (net (code "71") (name "Net-(LED17-GGND)") (class "Default")
      (node (ref "LED17") (pin "2") (pinfunction "GGND_2") (pintype "power_in"))
      (node (ref "U$51") (pin "11") (pinfunction "/OUT4_11") (pintype "bidirectional"))
    )
    (net (code "72") (name "Net-(LED17-RGND)") (class "Default")
      (node (ref "LED17") (pin "3") (pinfunction "RGND_3") (pintype "power_in"))
      (node (ref "U$51") (pin "9") (pinfunction "/OUT3_9") (pintype "bidirectional"))
    )
    (net (code "73") (name "Net-(LED18-BGND)") (class "Default")
      (node (ref "LED18") (pin "1") (pinfunction "BGND_1") (pintype "power_in"))
      (node (ref "U$51") (pin "15") (pinfunction "/OUT8_15") (pintype "bidirectional"))
    )
    (net (code "74") (name "Net-(LED18-GGND)") (class "Default")
      (node (ref "LED18") (pin "2") (pinfunction "GGND_2") (pintype "power_in"))
      (node (ref "U$51") (pin "14") (pinfunction "/OUT7_14") (pintype "bidirectional"))
    )
    (net (code "75") (name "Net-(LED18-RGND)") (class "Default")
      (node (ref "LED18") (pin "3") (pinfunction "RGND_3") (pintype "power_in"))
      (node (ref "U$51") (pin "13") (pinfunction "/OUT6_13") (pintype "bidirectional"))
    )
    (net (code "76") (name "Net-(LED19-BGND)") (class "Default")
      (node (ref "LED19") (pin "1") (pinfunction "BGND_1") (pintype "power_in"))
      (node (ref "U$51") (pin "18") (pinfunction "/OUT11_18") (pintype "bidirectional"))
    )
    (net (code "77") (name "Net-(LED19-GGND)") (class "Default")
      (node (ref "LED19") (pin "2") (pinfunction "GGND_2") (pintype "power_in"))
      (node (ref "U$51") (pin "17") (pinfunction "/OUT10_17") (pintype "bidirectional"))
    )
    (net (code "78") (name "Net-(LED19-RGND)") (class "Default")
      (node (ref "LED19") (pin "3") (pinfunction "RGND_3") (pintype "power_in"))
      (node (ref "U$51") (pin "16") (pinfunction "/OUT9_16") (pintype "bidirectional"))
    )
    (net (code "79") (name "Net-(LED20-BGND)") (class "Default")
      (node (ref "LED20") (pin "1") (pinfunction "BGND_1") (pintype "power_in"))
      (node (ref "U$51") (pin "22") (pinfunction "/OUT14_22") (pintype "bidirectional"))
    )
    (net (code "80") (name "Net-(LED20-GGND)") (class "Default")
      (node (ref "LED20") (pin "2") (pinfunction "GGND_2") (pintype "power_in"))
      (node (ref "U$51") (pin "21") (pinfunction "/OUT13_21") (pintype "bidirectional"))
    )
    (net (code "81") (name "Net-(LED20-RGND)") (class "Default")
      (node (ref "LED20") (pin "3") (pinfunction "RGND_3") (pintype "power_in"))
      (node (ref "U$51") (pin "20") (pinfunction "/OUT12_20") (pintype "bidirectional"))
    )
    (net (code "82") (name "Net-(U$30-REXT)") (class "Default")
      (node (ref "R4") (pin "1") (pinfunction "1_1") (pintype "passive"))
      (node (ref "U$30") (pin "1") (pinfunction "REXT_1") (pintype "bidirectional"))
    )
    (net (code "83") (name "Net-(U$33-REXT)") (class "Default")
      (node (ref "R5") (pin "1") (pinfunction "1_1") (pintype "passive"))
      (node (ref "U$33") (pin "1") (pinfunction "REXT_1") (pintype "bidirectional"))
    )
    (net (code "84") (name "Net-(U$36-REXT)") (class "Default")
      (node (ref "R6") (pin "1") (pinfunction "1_1") (pintype "passive"))
      (node (ref "U$36") (pin "1") (pinfunction "REXT_1") (pintype "bidirectional"))
    )
    (net (code "85") (name "Net-(U$51-REXT)") (class "Default")
      (node (ref "R15") (pin "1") (pinfunction "1_1") (pintype "passive"))
      (node (ref "U$51") (pin "1") (pinfunction "REXT_1") (pintype "bidirectional"))
    )
    (net (code "86") (name "SCL") (class "Default")
      (node (ref "R8") (pin "1") (pinfunction "1_1") (pintype "passive"))
      (node (ref "U$1") (pin "P$21") (pinfunction "PB10_P$21") (pintype "bidirectional"))
      (node (ref "U$30") (pin "26") (pinfunction "SCL_26") (pintype "bidirectional"))
      (node (ref "U$33") (pin "26") (pinfunction "SCL_26") (pintype "bidirectional"))
      (node (ref "U$36") (pin "26") (pinfunction "SCL_26") (pintype "bidirectional"))
      (node (ref "U$51") (pin "26") (pinfunction "SCL_26") (pintype "bidirectional"))
    )
    (net (code "87") (name "SDA") (class "Default")
      (node (ref "R7") (pin "1") (pinfunction "1_1") (pintype "passive"))
      (node (ref "U$1") (pin "P$22") (pinfunction "PB11_P$22") (pintype "bidirectional"))
      (node (ref "U$30") (pin "27") (pinfunction "SDA_27") (pintype "bidirectional"))
      (node (ref "U$33") (pin "27") (pinfunction "SDA_27") (pintype "bidirectional"))
      (node (ref "U$36") (pin "27") (pinfunction "SDA_27") (pintype "bidirectional"))
      (node (ref "U$51") (pin "27") (pinfunction "SDA_27") (pintype "bidirectional"))
    )
    (net (code "88") (name "SW1") (class "Default")
      (node (ref "C22") (pin "2") (pinfunction "P$2_2") (pintype "passive"))
      (node (ref "IC3") (pin "1") (pinfunction "I_1") (pintype "input"))
      (node (ref "R16") (pin "1") (pinfunction "1_1") (pintype "passive"))
      (node (ref "S1") (pin "3") (pinfunction "P_3") (pintype "passive"))
      (node (ref "S1") (pin "4") (pinfunction "P1_4") (pintype "passive"))
    )
    (net (code "89") (name "SW1S") (class "Default")
      (node (ref "IC3") (pin "2") (pinfunction "O_2") (pintype "output"))
      (node (ref "U$1") (pin "P$11") (pinfunction "PE8_P$11") (pintype "bidirectional"))
    )
    (net (code "90") (name "SW2") (class "Default")
      (node (ref "C23") (pin "2") (pinfunction "P$2_2") (pintype "passive"))
      (node (ref "IC3") (pin "3") (pinfunction "I_3") (pintype "input"))
      (node (ref "R17") (pin "1") (pinfunction "1_1") (pintype "passive"))
      (node (ref "S2") (pin "3") (pinfunction "P_3") (pintype "passive"))
      (node (ref "S2") (pin "4") (pinfunction "P1_4") (pintype "passive"))
    )
    (net (code "91") (name "SW2S") (class "Default")
      (node (ref "IC3") (pin "4") (pinfunction "O_4") (pintype "output"))
      (node (ref "U$1") (pin "P$9") (pinfunction "PB1_P$9") (pintype "bidirectional"))
    )
    (net (code "92") (name "SW3") (class "Default")
      (node (ref "C20") (pin "2") (pinfunction "P$2_2") (pintype "passive"))
      (node (ref "IC3") (pin "11") (pinfunction "I_11") (pintype "input"))
      (node (ref "R18") (pin "1") (pinfunction "1_1") (pintype "passive"))
      (node (ref "S3") (pin "3") (pinfunction "P_3") (pintype "passive"))
      (node (ref "S3") (pin "4") (pinfunction "P1_4") (pintype "passive"))
    )
    (net (code "93") (name "SW3S") (class "Default")
      (node (ref "IC3") (pin "10") (pinfunction "O_10") (pintype "output"))
      (node (ref "U$1") (pin "P$15") (pinfunction "PE12_P$15") (pintype "bidirectional"))
    )
    (net (code "94") (name "SW4") (class "Default")
      (node (ref "C19") (pin "2") (pinfunction "P$2_2") (pintype "passive"))
      (node (ref "IC3") (pin "13") (pinfunction "I_13") (pintype "input"))
      (node (ref "R19") (pin "1") (pinfunction "1_1") (pintype "passive"))
      (node (ref "S4") (pin "3") (pinfunction "P_3") (pintype "passive"))
      (node (ref "S4") (pin "4") (pinfunction "P1_4") (pintype "passive"))
    )
    (net (code "95") (name "SW4S") (class "Default")
      (node (ref "IC3") (pin "12") (pinfunction "O_12") (pintype "output"))
      (node (ref "U$1") (pin "P$13") (pinfunction "PE10_P$13") (pintype "bidirectional"))
    )
    (net (code "96") (name "SW5") (class "Default")
      (node (ref "C21") (pin "2") (pinfunction "P$2_2") (pintype "passive"))
      (node (ref "IC3") (pin "9") (pinfunction "I_9") (pintype "input"))
      (node (ref "R20") (pin "1") (pinfunction "1_1") (pintype "passive"))
      (node (ref "S5") (pin "3") (pinfunction "P_3") (pintype "passive"))
      (node (ref "S5") (pin "4") (pinfunction "P1_4") (pintype "passive"))
    )
    (net (code "97") (name "SW5S") (class "Default")
      (node (ref "IC3") (pin "8") (pinfunction "O_8") (pintype "output"))
      (node (ref "U$1") (pin "P$17") (pinfunction "PE14_P$17") (pintype "bidirectional"))
    )
    (net (code "98") (name "unconnected-(IC2F-O-Pad6)") (class "Default")
      (node (ref "IC2") (pin "6") (pinfunction "O_6") (pintype "output"))
    )
    (net (code "99") (name "unconnected-(IC3F-O-Pad6)") (class "Default")
      (node (ref "IC3") (pin "6") (pinfunction "O_6") (pintype "output"))
    )
    (net (code "100") (name "unconnected-(U$1A-PA4-PadP$2)") (class "Default")
      (node (ref "U$1") (pin "P$2") (pinfunction "PA4_P$2") (pintype "bidirectional"))
    )
    (net (code "101") (name "unconnected-(U$1A-PA6-PadP$4)") (class "Default")
      (node (ref "U$1") (pin "P$4") (pinfunction "PA6_P$4") (pintype "bidirectional"))
    )
    (net (code "102") (name "unconnected-(U$1A-PE7-PadP$10)") (class "Default")
      (node (ref "U$1") (pin "P$10") (pinfunction "PE7_P$10") (pintype "bidirectional"))
    )
    (net (code "103") (name "unconnected-(U$1A-PE9-PadP$12)") (class "Default")
      (node (ref "U$1") (pin "P$12") (pinfunction "PE9_P$12") (pintype "bidirectional"))
    )
    (net (code "104") (name "unconnected-(U$1A-PE11-PadP$14)") (class "Default")
      (node (ref "U$1") (pin "P$14") (pinfunction "PE11_P$14") (pintype "bidirectional"))
    )
    (net (code "105") (name "unconnected-(U$1A-PE13-PadP$16)") (class "Default")
      (node (ref "U$1") (pin "P$16") (pinfunction "PE13_P$16") (pintype "bidirectional"))
    )
    (net (code "106") (name "unconnected-(U$1A-PE15-PadP$18)") (class "Default")
      (node (ref "U$1") (pin "P$18") (pinfunction "PE15_P$18") (pintype "bidirectional"))
    )
    (net (code "107") (name "unconnected-(U$1B-PA8-PadP$39)") (class "Default")
      (node (ref "U$1") (pin "P$39") (pinfunction "PA8_P$39") (pintype "bidirectional"))
    )
    (net (code "108") (name "unconnected-(U$1B-PA9-PadP$40)") (class "Default")
      (node (ref "U$1") (pin "P$40") (pinfunction "PA9_P$40") (pintype "bidirectional"))
    )
    (net (code "109") (name "unconnected-(U$1B-PC6-PadP$35)") (class "Default")
      (node (ref "U$1") (pin "P$35") (pinfunction "PC6_P$35") (pintype "bidirectional"))
    )
    (net (code "110") (name "unconnected-(U$1B-PC7-PadP$36)") (class "Default")
      (node (ref "U$1") (pin "P$36") (pinfunction "PC7_P$36") (pintype "bidirectional"))
    )
    (net (code "111") (name "unconnected-(U$1B-PC8-PadP$37)") (class "Default")
      (node (ref "U$1") (pin "P$37") (pinfunction "PC8_P$37") (pintype "bidirectional"))
    )
    (net (code "112") (name "unconnected-(U$1B-PC9-PadP$38)") (class "Default")
      (node (ref "U$1") (pin "P$38") (pinfunction "PC9_P$38") (pintype "bidirectional"))
    )
    (net (code "113") (name "unconnected-(U$1B-PD8-PadP$27)") (class "Default")
      (node (ref "U$1") (pin "P$27") (pinfunction "PD8_P$27") (pintype "bidirectional"))
    )
    (net (code "114") (name "unconnected-(U$1B-PD10-PadP$29)") (class "Default")
      (node (ref "U$1") (pin "P$29") (pinfunction "PD10_P$29") (pintype "bidirectional"))
    )
    (net (code "115") (name "unconnected-(U$1B-PD11-PadP$30)") (class "Default")
      (node (ref "U$1") (pin "P$30") (pinfunction "PD11_P$30") (pintype "bidirectional"))
    )
    (net (code "116") (name "unconnected-(U$1B-PD12-PadP$31)") (class "Default")
      (node (ref "U$1") (pin "P$31") (pinfunction "PD12_P$31") (pintype "bidirectional"))
    )
    (net (code "117") (name "unconnected-(U$1B-PD13-PadP$32)") (class "Default")
      (node (ref "U$1") (pin "P$32") (pinfunction "PD13_P$32") (pintype "bidirectional"))
    )
    (net (code "118") (name "unconnected-(U$1B-PD14-PadP$33)") (class "Default")
      (node (ref "U$1") (pin "P$33") (pinfunction "PD14_P$33") (pintype "bidirectional"))
    )
    (net (code "119") (name "unconnected-(U$1B-PD15-PadP$34)") (class "Default")
      (node (ref "U$1") (pin "P$34") (pinfunction "PD15_P$34") (pintype "bidirectional"))
    )
    (net (code "120") (name "unconnected-(U$1C-PB4-PadP$54)") (class "Default")
      (node (ref "U$1") (pin "P$54") (pinfunction "PB4_P$54") (pintype "bidirectional"))
    )
    (net (code "121") (name "unconnected-(U$1C-PB5-PadP$55)") (class "Default")
      (node (ref "U$1") (pin "P$55") (pinfunction "PB5_P$55") (pintype "bidirectional"))
    )
    (net (code "122") (name "unconnected-(U$1C-PB6-PadP$56)") (class "Default")
      (node (ref "U$1") (pin "P$56") (pinfunction "PB6_P$56") (pintype "bidirectional"))
    )
    (net (code "123") (name "unconnected-(U$1C-PB7-PadP$57)") (class "Default")
      (node (ref "U$1") (pin "P$57") (pinfunction "PB7_P$57") (pintype "bidirectional"))
    )
    (net (code "124") (name "unconnected-(U$1C-PB8-PadP$58)") (class "Default")
      (node (ref "U$1") (pin "P$58") (pinfunction "PB8_P$58") (pintype "bidirectional"))
    )
    (net (code "125") (name "unconnected-(U$1C-PB9-PadP$59)") (class "Default")
      (node (ref "U$1") (pin "P$59") (pinfunction "PB9_P$59") (pintype "bidirectional"))
    )
    (net (code "126") (name "unconnected-(U$1C-PC10-PadP$45)") (class "Default")
      (node (ref "U$1") (pin "P$45") (pinfunction "PC10_P$45") (pintype "bidirectional"))
    )
    (net (code "127") (name "unconnected-(U$1C-PC11-PadP$46)") (class "Default")
      (node (ref "U$1") (pin "P$46") (pinfunction "PC11_P$46") (pintype "bidirectional"))
    )
    (net (code "128") (name "unconnected-(U$1C-PC12-PadP$47)") (class "Default")
      (node (ref "U$1") (pin "P$47") (pinfunction "PC12_P$47") (pintype "bidirectional"))
    )
    (net (code "129") (name "unconnected-(U$1C-PD2-PadP$48)") (class "Default")
      (node (ref "U$1") (pin "P$48") (pinfunction "PD2_P$48") (pintype "bidirectional"))
    )
    (net (code "130") (name "unconnected-(U$1C-PD3-PadP$49)") (class "Default")
      (node (ref "U$1") (pin "P$49") (pinfunction "PD3_P$49") (pintype "bidirectional"))
    )
    (net (code "131") (name "unconnected-(U$1C-PD4-PadP$50)") (class "Default")
      (node (ref "U$1") (pin "P$50") (pinfunction "PD4_P$50") (pintype "bidirectional"))
    )
    (net (code "132") (name "unconnected-(U$1C-PD5-PadP$51)") (class "Default")
      (node (ref "U$1") (pin "P$51") (pinfunction "PD5_P$51") (pintype "bidirectional"))
    )
    (net (code "133") (name "unconnected-(U$1C-PD6-PadP$52)") (class "Default")
      (node (ref "U$1") (pin "P$52") (pinfunction "PD6_P$52") (pintype "bidirectional"))
    )
    (net (code "134") (name "unconnected-(U$1C-PD7-PadP$53)") (class "Default")
      (node (ref "U$1") (pin "P$53") (pinfunction "PD7_P$53") (pintype "bidirectional"))
    )
    (net (code "135") (name "unconnected-(U$1C-PE0-PadP$60)") (class "Default")
      (node (ref "U$1") (pin "P$60") (pinfunction "PE0_P$60") (pintype "bidirectional"))
    )
    (net (code "136") (name "unconnected-(U$1C-PE1-PadP$61)") (class "Default")
      (node (ref "U$1") (pin "P$61") (pinfunction "PE1_P$61") (pintype "bidirectional"))
    )
    (net (code "137") (name "unconnected-(U$1D-PA0-PadP$75)") (class "Default")
      (node (ref "U$1") (pin "P$75") (pinfunction "PA0_P$75") (pintype "bidirectional"))
    )
    (net (code "138") (name "unconnected-(U$1D-PA1-PadP$76)") (class "Default")
      (node (ref "U$1") (pin "P$76") (pinfunction "PA1_P$76") (pintype "bidirectional"))
    )
    (net (code "139") (name "unconnected-(U$1D-PA2-PadP$77)") (class "Default")
      (node (ref "U$1") (pin "P$77") (pinfunction "PA2_P$77") (pintype "bidirectional"))
    )
    (net (code "140") (name "unconnected-(U$1D-PC0-PadP$71)") (class "Default")
      (node (ref "U$1") (pin "P$71") (pinfunction "PC0_P$71") (pintype "bidirectional"))
    )
    (net (code "141") (name "unconnected-(U$1D-PC1-PadP$72)") (class "Default")
      (node (ref "U$1") (pin "P$72") (pinfunction "PC1_P$72") (pintype "bidirectional"))
    )
    (net (code "142") (name "unconnected-(U$1D-PC2-PadP$73)") (class "Default")
      (node (ref "U$1") (pin "P$73") (pinfunction "PC2_P$73") (pintype "bidirectional"))
    )
    (net (code "143") (name "unconnected-(U$1D-PC3-PadP$74)") (class "Default")
      (node (ref "U$1") (pin "P$74") (pinfunction "PC3_P$74") (pintype "bidirectional"))
    )
    (net (code "144") (name "unconnected-(U$1D-PC13-PadP$68)") (class "Default")
      (node (ref "U$1") (pin "P$68") (pinfunction "PC13_P$68") (pintype "bidirectional"))
    )
    (net (code "145") (name "unconnected-(U$1D-PE2-PadP$63)") (class "Default")
      (node (ref "U$1") (pin "P$63") (pinfunction "PE2_P$63") (pintype "bidirectional"))
    )
    (net (code "146") (name "unconnected-(U$1D-PE3-PadP$64)") (class "Default")
      (node (ref "U$1") (pin "P$64") (pinfunction "PE3_P$64") (pintype "bidirectional"))
    )
    (net (code "147") (name "unconnected-(U$1D-PE4-PadP$65)") (class "Default")
      (node (ref "U$1") (pin "P$65") (pinfunction "PE4_P$65") (pintype "bidirectional"))
    )
    (net (code "148") (name "unconnected-(U$1D-PE5-PadP$66)") (class "Default")
      (node (ref "U$1") (pin "P$66") (pinfunction "PE5_P$66") (pintype "bidirectional"))
    )
    (net (code "149") (name "unconnected-(U$1D-PE6-PadP$67)") (class "Default")
      (node (ref "U$1") (pin "P$67") (pinfunction "PE6_P$67") (pintype "bidirectional"))
    )
    (net (code "150") (name "unconnected-(U$30-{slash}OUT15-Pad23)") (class "Default")
      (node (ref "U$30") (pin "23") (pinfunction "/OUT15_23") (pintype "bidirectional"))
    )
    (net (code "151") (name "unconnected-(U$33-{slash}OUT15-Pad23)") (class "Default")
      (node (ref "U$33") (pin "23") (pinfunction "/OUT15_23") (pintype "bidirectional"))
    )
    (net (code "152") (name "unconnected-(U$36-{slash}OUT15-Pad23)") (class "Default")
      (node (ref "U$36") (pin "23") (pinfunction "/OUT15_23") (pintype "bidirectional"))
    )
    (net (code "153") (name "unconnected-(U$51-{slash}OUT15-Pad23)") (class "Default")
      (node (ref "U$51") (pin "23") (pinfunction "/OUT15_23") (pintype "bidirectional"))
    )
  )
)
